# Barker_project_02.net
KiCad netlist of a schematic drawn in EAGLE
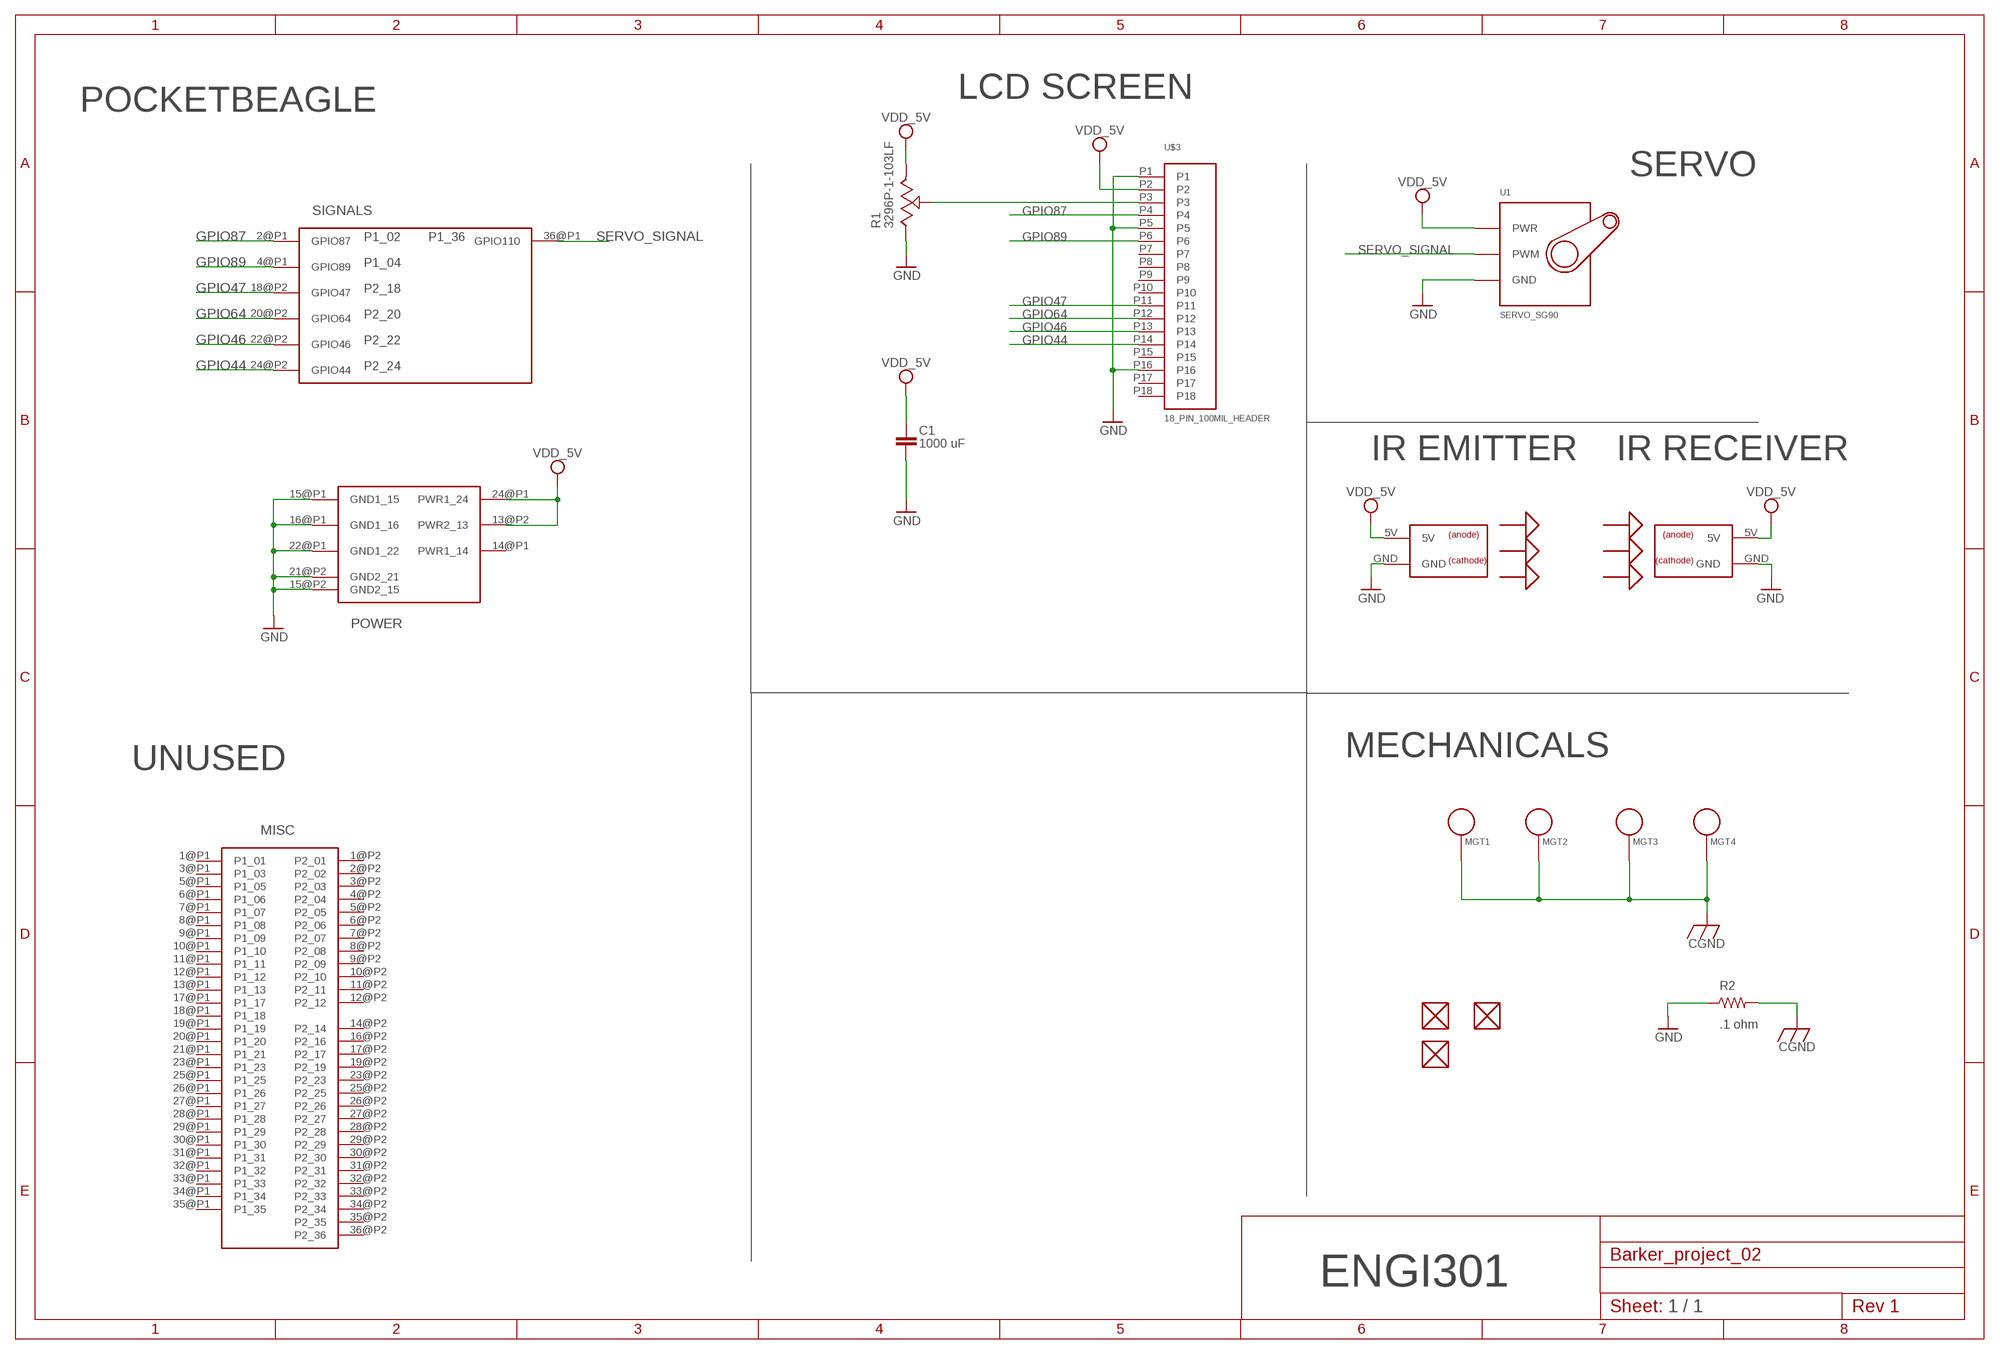
[diagram p0: schematic, sheet 1]

(export (version "E")
  (design (tool "Eeschema 10.0.6"))
  (components
    (comp (ref "C1")
      (value "1000 uF")
      (footprint "eagle-import:C0402")
      (libsource (lib "eagle-import") (part "C_C0402"))
    )
    (comp (ref "FUD1")
      (value "FIDUCIAL")
      (footprint "eagle-import:FIDUCIAL_40MIL")
      (libsource (lib "eagle-import") (part "FIDUCIAL"))
    )
    (comp (ref "FUD2")
      (value "FIDUCIAL")
      (footprint "eagle-import:FIDUCIAL_40MIL")
      (libsource (lib "eagle-import") (part "FIDUCIAL"))
    )
    (comp (ref "FUD3")
      (value "FIDUCIAL")
      (footprint "eagle-import:FIDUCIAL_40MIL")
      (libsource (lib "eagle-import") (part "FIDUCIAL"))
    )
    (comp (ref "MGT1")
      (value "MOUNTING_HOLE")
      (footprint "eagle-import:MOUNTING_HOLE")
      (libsource (lib "eagle-import") (part "MOUNTING_HOLE"))
    )
    (comp (ref "MGT2")
      (value "MOUNTING_HOLE")
      (footprint "eagle-import:MOUNTING_HOLE")
      (libsource (lib "eagle-import") (part "MOUNTING_HOLE"))
    )
    (comp (ref "MGT3")
      (value "MOUNTING_HOLE")
      (footprint "eagle-import:MOUNTING_HOLE")
      (libsource (lib "eagle-import") (part "MOUNTING_HOLE"))
    )
    (comp (ref "MGT4")
      (value "MOUNTING_HOLE")
      (footprint "eagle-import:MOUNTING_HOLE")
      (libsource (lib "eagle-import") (part "MOUNTING_HOLE"))
    )
    (comp (ref "R1")
      (value "3296P-1-103LF")
      (footprint "eagle-import:TRIM_3296P-1-103LF")
      (fields (field (name "MF") "Bourns"))
      (libsource (lib "eagle-import") (part "3296P-1-103LF"))
    )
    (comp (ref "R2")
      (value ".1 ohm")
      (footprint "eagle-import:R0402")
      (libsource (lib "eagle-import") (part "R_R0402"))
    )
    (comp (ref "U$3")
      (value "18_PIN_100MIL_HEADER")
      (footprint "eagle-import:18_PIN_100MIL_HEADER")
      (libsource (lib "eagle-import") (part "18_PIN_100MIL_HEADER"))
    )
    (comp (ref "U1")
      (value "SERVO_SG90")
      (footprint "eagle-import:SERVO-X1")
      (libsource (lib "eagle-import") (part "SERVO_SG90"))
    )
    (comp (ref "U2")
      (value "POCKETBEAGLE")
      (footprint "eagle-import:POCKETBEAGLE")
      (libsource (lib "eagle-import") (part "POCKETBEAGLE"))
    )
    (comp (ref "U3")
      (value "IR_EMITTER")
      (footprint "eagle-import:2_PIN_100MIL_HEADER")
      (libsource (lib "eagle-import") (part "IR_EMITTER"))
    )
    (comp (ref "U4")
      (value "IR_DETECTOR")
      (footprint "eagle-import:2_PIN_100MIL_HEADER")
      (libsource (lib "eagle-import") (part "IR_DETECTOR"))
    )
  )
  (nets
    (net (code "1") (name "/GPIO44") (class "Default")
      (node (ref "U$3") (pin "P14") (pinfunction "P14_P14") (pintype "bidirectional"))
      (node (ref "U2") (pin "24@P2") (pinfunction "GPIO44_24@P2") (pintype "bidirectional"))
    )
    (net (code "2") (name "/GPIO46") (class "Default")
      (node (ref "U$3") (pin "P13") (pinfunction "P13_P13") (pintype "bidirectional"))
      (node (ref "U2") (pin "22@P2") (pinfunction "GPIO46_22@P2") (pintype "bidirectional"))
    )
    (net (code "3") (name "/GPIO47") (class "Default")
      (node (ref "U$3") (pin "P11") (pinfunction "P11_P11") (pintype "bidirectional"))
      (node (ref "U2") (pin "18@P2") (pinfunction "GPIO47_18@P2") (pintype "bidirectional"))
    )
    (net (code "4") (name "/GPIO64") (class "Default")
      (node (ref "U$3") (pin "P12") (pinfunction "P12_P12") (pintype "bidirectional"))
      (node (ref "U2") (pin "20@P2") (pinfunction "GPIO64_20@P2") (pintype "bidirectional"))
    )
    (net (code "5") (name "/GPIO87") (class "Default")
      (node (ref "U$3") (pin "P4") (pinfunction "P4_P4") (pintype "bidirectional"))
      (node (ref "U2") (pin "2@P1") (pinfunction "GPIO87_2@P1") (pintype "bidirectional"))
    )
    (net (code "6") (name "/GPIO89") (class "Default")
      (node (ref "U$3") (pin "P6") (pinfunction "P6_P6") (pintype "bidirectional"))
      (node (ref "U2") (pin "4@P1") (pinfunction "GPIO89_4@P1") (pintype "bidirectional"))
    )
    (net (code "7") (name "/SERVO_SIGNAL") (class "Default")
      (node (ref "U1") (pin "SIG") (pinfunction "PWM_SIG") (pintype "bidirectional"))
      (node (ref "U2") (pin "36@P1") (pinfunction "GPIO110_36@P1") (pintype "bidirectional"))
    )
    (net (code "8") (name "CGND") (class "Default")
      (node (ref "MGT1") (pin "P$1") (pinfunction "P$1_P$1") (pintype "bidirectional"))
      (node (ref "MGT2") (pin "P$1") (pinfunction "P$1_P$1") (pintype "bidirectional"))
      (node (ref "MGT3") (pin "P$1") (pinfunction "P$1_P$1") (pintype "bidirectional"))
      (node (ref "MGT4") (pin "P$1") (pinfunction "P$1_P$1") (pintype "bidirectional"))
      (node (ref "R2") (pin "2") (pinfunction "2_2") (pintype "passive"))
    )
    (net (code "9") (name "GND") (class "Default")
      (node (ref "C1") (pin "2") (pinfunction "2_2") (pintype "passive"))
      (node (ref "R1") (pin "1") (pinfunction "CCW_1") (pintype "passive"))
      (node (ref "R2") (pin "1") (pinfunction "1_1") (pintype "passive"))
      (node (ref "U$3") (pin "P1") (pinfunction "P1_P1") (pintype "bidirectional"))
      (node (ref "U$3") (pin "P16") (pinfunction "P16_P16") (pintype "bidirectional"))
      (node (ref "U$3") (pin "P5") (pinfunction "P5_P5") (pintype "bidirectional"))
      (node (ref "U1") (pin "GND") (pinfunction "GND_GND") (pintype "bidirectional"))
      (node (ref "U2") (pin "15@P1") (pinfunction "GND1_15_15@P1") (pintype "bidirectional"))
      (node (ref "U2") (pin "15@P2") (pinfunction "GND2_15_15@P2") (pintype "bidirectional"))
      (node (ref "U2") (pin "16@P1") (pinfunction "GND1_16_16@P1") (pintype "bidirectional"))
      (node (ref "U2") (pin "21@P2") (pinfunction "GND2_21_21@P2") (pintype "bidirectional"))
      (node (ref "U2") (pin "22@P1") (pinfunction "GND1_22_22@P1") (pintype "bidirectional"))
      (node (ref "U3") (pin "GND") (pinfunction "GND_GND") (pintype "bidirectional"))
      (node (ref "U4") (pin "GND") (pinfunction "GND_GND") (pintype "bidirectional"))
    )
    (net (code "10") (name "Net-(R1-WIPER)") (class "Default")
      (node (ref "R1") (pin "2") (pinfunction "WIPER_2") (pintype "passive"))
      (node (ref "U$3") (pin "P3") (pinfunction "P3_P3") (pintype "bidirectional"))
    )
    (net (code "11") (name "VDD_5V") (class "Default")
      (node (ref "C1") (pin "1") (pinfunction "1_1") (pintype "passive"))
      (node (ref "R1") (pin "3") (pinfunction "CW_3") (pintype "passive"))
      (node (ref "U$3") (pin "P2") (pinfunction "P2_P2") (pintype "bidirectional"))
      (node (ref "U1") (pin "PWR") (pinfunction "PWR_PWR") (pintype "bidirectional"))
      (node (ref "U2") (pin "13@P2") (pinfunction "PWR2_13_13@P2") (pintype "bidirectional"))
      (node (ref "U2") (pin "24@P1") (pinfunction "PWR1_24_24@P1") (pintype "bidirectional"))
      (node (ref "U3") (pin "5V") (pinfunction "5V_5V") (pintype "bidirectional"))
      (node (ref "U4") (pin "5V") (pinfunction "5V_5V") (pintype "bidirectional"))
    )
    (net (code "12") (name "unconnected-(FUD1-PadP$1)") (class "Default")
      (node (ref "FUD1") (pin "P$1") (pinfunction "P$1_P$1") (pintype "no_connect"))
    )
    (net (code "13") (name "unconnected-(FUD2-PadP$1)") (class "Default")
      (node (ref "FUD2") (pin "P$1") (pinfunction "P$1_P$1") (pintype "no_connect"))
    )
    (net (code "14") (name "unconnected-(FUD3-PadP$1)") (class "Default")
      (node (ref "FUD3") (pin "P$1") (pinfunction "P$1_P$1") (pintype "no_connect"))
    )
    (net (code "15") (name "unconnected-(U$3-PadP7)") (class "Default")
      (node (ref "U$3") (pin "P7") (pinfunction "P7_P7") (pintype "bidirectional"))
    )
    (net (code "16") (name "unconnected-(U$3-PadP8)") (class "Default")
      (node (ref "U$3") (pin "P8") (pinfunction "P8_P8") (pintype "bidirectional"))
    )
    (net (code "17") (name "unconnected-(U$3-PadP9)") (class "Default")
      (node (ref "U$3") (pin "P9") (pinfunction "P9_P9") (pintype "bidirectional"))
    )
    (net (code "18") (name "unconnected-(U$3-PadP10)") (class "Default")
      (node (ref "U$3") (pin "P10") (pinfunction "P10_P10") (pintype "bidirectional"))
    )
    (net (code "19") (name "unconnected-(U$3-PadP15)") (class "Default")
      (node (ref "U$3") (pin "P15") (pinfunction "P15_P15") (pintype "bidirectional"))
    )
    (net (code "20") (name "unconnected-(U$3-PadP17)") (class "Default")
      (node (ref "U$3") (pin "P17") (pinfunction "P17_P17") (pintype "bidirectional"))
    )
    (net (code "21") (name "unconnected-(U$3-PadP18)") (class "Default")
      (node (ref "U$3") (pin "P18") (pinfunction "P18_P18") (pintype "bidirectional"))
    )
    (net (code "22") (name "unconnected-(U2B-PWR1_14-Pad14@P1)") (class "Default")
      (node (ref "U2") (pin "14@P1") (pinfunction "PWR1_14_14@P1") (pintype "bidirectional"))
    )
    (net (code "23") (name "unconnected-(U2C-P1_01-Pad1@P1)") (class "Default")
      (node (ref "U2") (pin "1@P1") (pinfunction "P1_01_1@P1") (pintype "bidirectional"))
    )
    (net (code "24") (name "unconnected-(U2C-P1_03-Pad3@P1)") (class "Default")
      (node (ref "U2") (pin "3@P1") (pinfunction "P1_03_3@P1") (pintype "bidirectional"))
    )
    (net (code "25") (name "unconnected-(U2C-P1_05-Pad5@P1)") (class "Default")
      (node (ref "U2") (pin "5@P1") (pinfunction "P1_05_5@P1") (pintype "bidirectional"))
    )
    (net (code "26") (name "unconnected-(U2C-P1_06-Pad6@P1)") (class "Default")
      (node (ref "U2") (pin "6@P1") (pinfunction "P1_06_6@P1") (pintype "bidirectional"))
    )
    (net (code "27") (name "unconnected-(U2C-P1_07-Pad7@P1)") (class "Default")
      (node (ref "U2") (pin "7@P1") (pinfunction "P1_07_7@P1") (pintype "bidirectional"))
    )
    (net (code "28") (name "unconnected-(U2C-P1_08-Pad8@P1)") (class "Default")
      (node (ref "U2") (pin "8@P1") (pinfunction "P1_08_8@P1") (pintype "bidirectional"))
    )
    (net (code "29") (name "unconnected-(U2C-P1_09-Pad9@P1)") (class "Default")
      (node (ref "U2") (pin "9@P1") (pinfunction "P1_09_9@P1") (pintype "bidirectional"))
    )
    (net (code "30") (name "unconnected-(U2C-P1_10-Pad10@P1)") (class "Default")
      (node (ref "U2") (pin "10@P1") (pinfunction "P1_10_10@P1") (pintype "bidirectional"))
    )
    (net (code "31") (name "unconnected-(U2C-P1_11-Pad11@P1)") (class "Default")
      (node (ref "U2") (pin "11@P1") (pinfunction "P1_11_11@P1") (pintype "bidirectional"))
    )
    (net (code "32") (name "unconnected-(U2C-P1_12-Pad12@P1)") (class "Default")
      (node (ref "U2") (pin "12@P1") (pinfunction "P1_12_12@P1") (pintype "bidirectional"))
    )
    (net (code "33") (name "unconnected-(U2C-P1_13-Pad13@P1)") (class "Default")
      (node (ref "U2") (pin "13@P1") (pinfunction "P1_13_13@P1") (pintype "bidirectional"))
    )
    (net (code "34") (name "unconnected-(U2C-P1_17-Pad17@P1)") (class "Default")
      (node (ref "U2") (pin "17@P1") (pinfunction "P1_17_17@P1") (pintype "bidirectional"))
    )
    (net (code "35") (name "unconnected-(U2C-P1_18-Pad18@P1)") (class "Default")
      (node (ref "U2") (pin "18@P1") (pinfunction "P1_18_18@P1") (pintype "bidirectional"))
    )
    (net (code "36") (name "unconnected-(U2C-P1_19-Pad19@P1)") (class "Default")
      (node (ref "U2") (pin "19@P1") (pinfunction "P1_19_19@P1") (pintype "bidirectional"))
    )
    (net (code "37") (name "unconnected-(U2C-P1_20-Pad20@P1)") (class "Default")
      (node (ref "U2") (pin "20@P1") (pinfunction "P1_20_20@P1") (pintype "bidirectional"))
    )
    (net (code "38") (name "unconnected-(U2C-P1_21-Pad21@P1)") (class "Default")
      (node (ref "U2") (pin "21@P1") (pinfunction "P1_21_21@P1") (pintype "bidirectional"))
    )
    (net (code "39") (name "unconnected-(U2C-P1_23-Pad23@P1)") (class "Default")
      (node (ref "U2") (pin "23@P1") (pinfunction "P1_23_23@P1") (pintype "bidirectional"))
    )
    (net (code "40") (name "unconnected-(U2C-P1_25-Pad25@P1)") (class "Default")
      (node (ref "U2") (pin "25@P1") (pinfunction "P1_25_25@P1") (pintype "bidirectional"))
    )
    (net (code "41") (name "unconnected-(U2C-P1_26-Pad26@P1)") (class "Default")
      (node (ref "U2") (pin "26@P1") (pinfunction "P1_26_26@P1") (pintype "bidirectional"))
    )
    (net (code "42") (name "unconnected-(U2C-P1_27-Pad27@P1)") (class "Default")
      (node (ref "U2") (pin "27@P1") (pinfunction "P1_27_27@P1") (pintype "bidirectional"))
    )
    (net (code "43") (name "unconnected-(U2C-P1_28-Pad28@P1)") (class "Default")
      (node (ref "U2") (pin "28@P1") (pinfunction "P1_28_28@P1") (pintype "bidirectional"))
    )
    (net (code "44") (name "unconnected-(U2C-P1_29-Pad29@P1)") (class "Default")
      (node (ref "U2") (pin "29@P1") (pinfunction "P1_29_29@P1") (pintype "bidirectional"))
    )
    (net (code "45") (name "unconnected-(U2C-P1_30-Pad30@P1)") (class "Default")
      (node (ref "U2") (pin "30@P1") (pinfunction "P1_30_30@P1") (pintype "bidirectional"))
    )
    (net (code "46") (name "unconnected-(U2C-P1_31-Pad31@P1)") (class "Default")
      (node (ref "U2") (pin "31@P1") (pinfunction "P1_31_31@P1") (pintype "bidirectional"))
    )
    (net (code "47") (name "unconnected-(U2C-P1_32-Pad32@P1)") (class "Default")
      (node (ref "U2") (pin "32@P1") (pinfunction "P1_32_32@P1") (pintype "bidirectional"))
    )
    (net (code "48") (name "unconnected-(U2C-P1_33-Pad33@P1)") (class "Default")
      (node (ref "U2") (pin "33@P1") (pinfunction "P1_33_33@P1") (pintype "bidirectional"))
    )
    (net (code "49") (name "unconnected-(U2C-P1_34-Pad34@P1)") (class "Default")
      (node (ref "U2") (pin "34@P1") (pinfunction "P1_34_34@P1") (pintype "bidirectional"))
    )
    (net (code "50") (name "unconnected-(U2C-P1_35-Pad35@P1)") (class "Default")
      (node (ref "U2") (pin "35@P1") (pinfunction "P1_35_35@P1") (pintype "bidirectional"))
    )
    (net (code "51") (name "unconnected-(U2C-P2_01-Pad1@P2)") (class "Default")
      (node (ref "U2") (pin "1@P2") (pinfunction "P2_01_1@P2") (pintype "bidirectional"))
    )
    (net (code "52") (name "unconnected-(U2C-P2_02-Pad2@P2)") (class "Default")
      (node (ref "U2") (pin "2@P2") (pinfunction "P2_02_2@P2") (pintype "bidirectional"))
    )
    (net (code "53") (name "unconnected-(U2C-P2_03-Pad3@P2)") (class "Default")
      (node (ref "U2") (pin "3@P2") (pinfunction "P2_03_3@P2") (pintype "bidirectional"))
    )
    (net (code "54") (name "unconnected-(U2C-P2_04-Pad4@P2)") (class "Default")
      (node (ref "U2") (pin "4@P2") (pinfunction "P2_04_4@P2") (pintype "bidirectional"))
    )
    (net (code "55") (name "unconnected-(U2C-P2_05-Pad5@P2)") (class "Default")
      (node (ref "U2") (pin "5@P2") (pinfunction "P2_05_5@P2") (pintype "bidirectional"))
    )
    (net (code "56") (name "unconnected-(U2C-P2_06-Pad6@P2)") (class "Default")
      (node (ref "U2") (pin "6@P2") (pinfunction "P2_06_6@P2") (pintype "bidirectional"))
    )
    (net (code "57") (name "unconnected-(U2C-P2_07-Pad7@P2)") (class "Default")
      (node (ref "U2") (pin "7@P2") (pinfunction "P2_07_7@P2") (pintype "bidirectional"))
    )
    (net (code "58") (name "unconnected-(U2C-P2_08-Pad8@P2)") (class "Default")
      (node (ref "U2") (pin "8@P2") (pinfunction "P2_08_8@P2") (pintype "bidirectional"))
    )
    (net (code "59") (name "unconnected-(U2C-P2_09-Pad9@P2)") (class "Default")
      (node (ref "U2") (pin "9@P2") (pinfunction "P2_09_9@P2") (pintype "bidirectional"))
    )
    (net (code "60") (name "unconnected-(U2C-P2_10-Pad10@P2)") (class "Default")
      (node (ref "U2") (pin "10@P2") (pinfunction "P2_10_10@P2") (pintype "bidirectional"))
    )
    (net (code "61") (name "unconnected-(U2C-P2_11-Pad11@P2)") (class "Default")
      (node (ref "U2") (pin "11@P2") (pinfunction "P2_11_11@P2") (pintype "bidirectional"))
    )
    (net (code "62") (name "unconnected-(U2C-P2_12-Pad12@P2)") (class "Default")
      (node (ref "U2") (pin "12@P2") (pinfunction "P2_12_12@P2") (pintype "bidirectional"))
    )
    (net (code "63") (name "unconnected-(U2C-P2_14-Pad14@P2)") (class "Default")
      (node (ref "U2") (pin "14@P2") (pinfunction "P2_14_14@P2") (pintype "bidirectional"))
    )
    (net (code "64") (name "unconnected-(U2C-P2_16-Pad16@P2)") (class "Default")
      (node (ref "U2") (pin "16@P2") (pinfunction "P2_16_16@P2") (pintype "bidirectional"))
    )
    (net (code "65") (name "unconnected-(U2C-P2_17-Pad17@P2)") (class "Default")
      (node (ref "U2") (pin "17@P2") (pinfunction "P2_17_17@P2") (pintype "bidirectional"))
    )
    (net (code "66") (name "unconnected-(U2C-P2_19-Pad19@P2)") (class "Default")
      (node (ref "U2") (pin "19@P2") (pinfunction "P2_19_19@P2") (pintype "bidirectional"))
    )
    (net (code "67") (name "unconnected-(U2C-P2_23-Pad23@P2)") (class "Default")
      (node (ref "U2") (pin "23@P2") (pinfunction "P2_23_23@P2") (pintype "bidirectional"))
    )
    (net (code "68") (name "unconnected-(U2C-P2_25-Pad25@P2)") (class "Default")
      (node (ref "U2") (pin "25@P2") (pinfunction "P2_25_25@P2") (pintype "bidirectional"))
    )
    (net (code "69") (name "unconnected-(U2C-P2_26-Pad26@P2)") (class "Default")
      (node (ref "U2") (pin "26@P2") (pinfunction "P2_26_26@P2") (pintype "bidirectional"))
    )
    (net (code "70") (name "unconnected-(U2C-P2_27-Pad27@P2)") (class "Default")
      (node (ref "U2") (pin "27@P2") (pinfunction "P2_27_27@P2") (pintype "bidirectional"))
    )
    (net (code "71") (name "unconnected-(U2C-P2_28-Pad28@P2)") (class "Default")
      (node (ref "U2") (pin "28@P2") (pinfunction "P2_28_28@P2") (pintype "bidirectional"))
    )
    (net (code "72") (name "unconnected-(U2C-P2_29-Pad29@P2)") (class "Default")
      (node (ref "U2") (pin "29@P2") (pinfunction "P2_29_29@P2") (pintype "bidirectional"))
    )
    (net (code "73") (name "unconnected-(U2C-P2_30-Pad30@P2)") (class "Default")
      (node (ref "U2") (pin "30@P2") (pinfunction "P2_30_30@P2") (pintype "bidirectional"))
    )
    (net (code "74") (name "unconnected-(U2C-P2_31-Pad31@P2)") (class "Default")
      (node (ref "U2") (pin "31@P2") (pinfunction "P2_31_31@P2") (pintype "bidirectional"))
    )
    (net (code "75") (name "unconnected-(U2C-P2_32-Pad32@P2)") (class "Default")
      (node (ref "U2") (pin "32@P2") (pinfunction "P2_32_32@P2") (pintype "bidirectional"))
    )
    (net (code "76") (name "unconnected-(U2C-P2_33-Pad33@P2)") (class "Default")
      (node (ref "U2") (pin "33@P2") (pinfunction "P2_33_33@P2") (pintype "bidirectional"))
    )
    (net (code "77") (name "unconnected-(U2C-P2_34-Pad34@P2)") (class "Default")
      (node (ref "U2") (pin "34@P2") (pinfunction "P2_34_34@P2") (pintype "bidirectional"))
    )
    (net (code "78") (name "unconnected-(U2C-P2_35-Pad35@P2)") (class "Default")
      (node (ref "U2") (pin "35@P2") (pinfunction "P2_35_35@P2") (pintype "bidirectional"))
    )
    (net (code "79") (name "unconnected-(U2C-P2_36-Pad36@P2)") (class "Default")
      (node (ref "U2") (pin "36@P2") (pinfunction "P2_36_36@P2") (pintype "bidirectional"))
    )
  )
)
